# Mouse_Send_SCH.net
KiCad netlist of a schematic drawn in Altium Designer
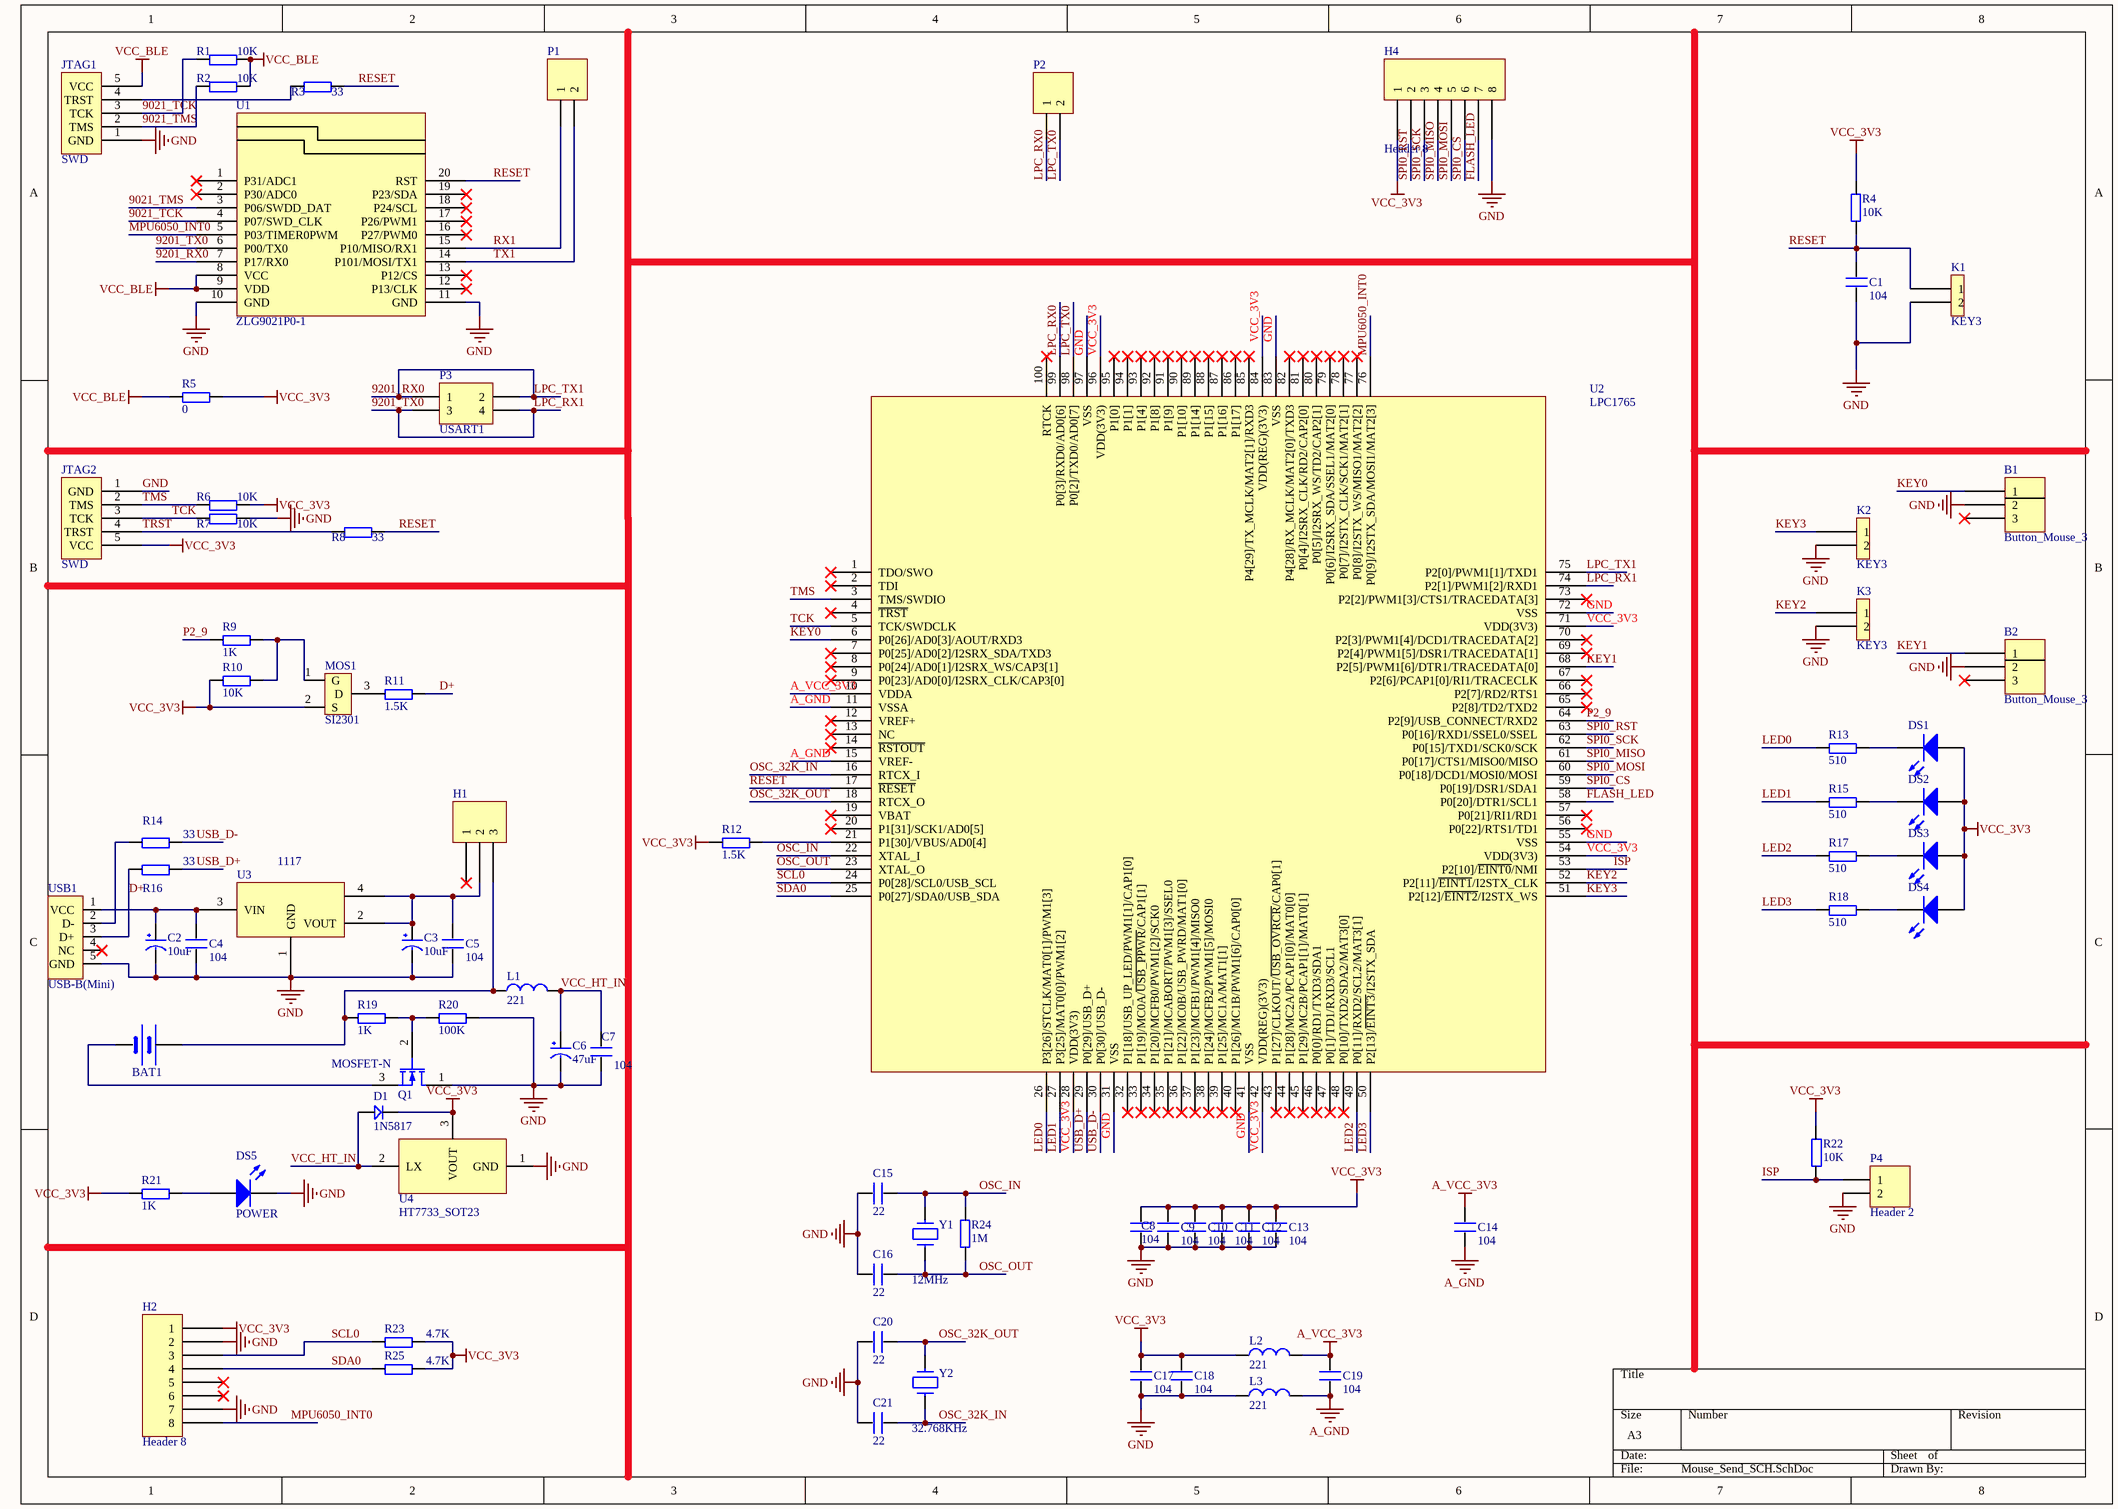
[diagram p0: Mouse_Send_SCH.SchDoc]

(export (version "E")
  (design (tool "Eeschema 10.0.6"))
  (components
    (comp (ref "B1")
      (value "Button_Mouse_3")
      (footprint "Button_Mouse_3")
      (libsource (lib "MY_SCH_Lib") (part "Button_Mouse_3"))
    )
    (comp (ref "B2")
      (value "Button_Mouse_3")
      (footprint "Button_Mouse_3")
      (libsource (lib "MY_SCH_Lib") (part "Button_Mouse_3"))
    )
    (comp (ref "BAT1") (value "BATT") (footprint "BAT_NUM5_2") (libsource (lib "MY_SCH_Lib") (part "BAT")))
    (comp (ref "C1") (value "104") (footprint "0603P") (libsource (lib "MY_SCH_Lib") (part "C")))
    (comp (ref "C2") (value "10uF") (footprint "TAJ_A") (libsource (lib "MY_SCH_Lib") (part "CAP")))
    (comp (ref "C3") (value "10uF") (footprint "TAJ_A") (libsource (lib "MY_SCH_Lib") (part "CAP")))
    (comp (ref "C4") (value "104") (footprint "0603P") (libsource (lib "MY_SCH_Lib") (part "C")))
    (comp (ref "C5") (value "104") (footprint "0603P") (libsource (lib "MY_SCH_Lib") (part "C")))
    (comp (ref "C6") (value "47uF") (footprint "TAJ_A") (libsource (lib "MY_SCH_Lib") (part "CAP")))
    (comp (ref "C7") (value "104") (footprint "0603P") (libsource (lib "MY_SCH_Lib") (part "C")))
    (comp (ref "C8") (value "104") (footprint "0603P") (libsource (lib "MY_SCH_Lib") (part "C")))
    (comp (ref "C9") (value "104") (footprint "0603P") (libsource (lib "MY_SCH_Lib") (part "C")))
    (comp (ref "C10") (value "104") (footprint "0603P") (libsource (lib "MY_SCH_Lib") (part "C")))
    (comp (ref "C11") (value "104") (footprint "0603P") (libsource (lib "MY_SCH_Lib") (part "C")))
    (comp (ref "C12") (value "104") (footprint "0603P") (libsource (lib "MY_SCH_Lib") (part "C")))
    (comp (ref "C13") (value "104") (footprint "0603P") (libsource (lib "MY_SCH_Lib") (part "C")))
    (comp (ref "C14") (value "104") (footprint "0603P") (libsource (lib "MY_SCH_Lib") (part "C")))
    (comp (ref "C15") (value "22") (footprint "0603P") (libsource (lib "MY_SCH_Lib") (part "C")))
    (comp (ref "C16") (value "22") (footprint "0603P") (libsource (lib "MY_SCH_Lib") (part "C")))
    (comp (ref "C17") (value "104") (footprint "0603P") (libsource (lib "MY_SCH_Lib") (part "C")))
    (comp (ref "C18") (value "104") (footprint "0603P") (libsource (lib "MY_SCH_Lib") (part "C")))
    (comp (ref "C19") (value "104") (footprint "0603P") (libsource (lib "MY_SCH_Lib") (part "C")))
    (comp (ref "C20") (value "22") (footprint "0603P") (libsource (lib "MY_SCH_Lib") (part "C")))
    (comp (ref "C21") (value "22") (footprint "0603P") (libsource (lib "MY_SCH_Lib") (part "C")))
    (comp (ref "D1") (value "1N5817") (footprint "DIODE_SOP") (libsource (lib "MY_SCH_Lib") (part "D")))
    (comp (ref "DS1")
      (value "~")
      (footprint "SMDLED")
      (description "Typical RED, GREEN, YELLOW, AMBER GaAs LED")
      (fields (field (name "PUBLISHER") "Altium Limited"))
      (libsource (lib "MY_SCH_Lib") (part "LED2"))
    )
    (comp (ref "DS2")
      (value "~")
      (footprint "SMDLED")
      (description "Typical RED, GREEN, YELLOW, AMBER GaAs LED")
      (fields (field (name "PUBLISHER") "Altium Limited"))
      (libsource (lib "MY_SCH_Lib") (part "LED2"))
    )
    (comp (ref "DS3")
      (value "~")
      (footprint "SMDLED")
      (description "Typical RED, GREEN, YELLOW, AMBER GaAs LED")
      (fields (field (name "PUBLISHER") "Altium Limited"))
      (libsource (lib "MY_SCH_Lib") (part "LED2"))
    )
    (comp (ref "DS4")
      (value "~")
      (footprint "SMDLED")
      (description "Typical RED, GREEN, YELLOW, AMBER GaAs LED")
      (fields (field (name "PUBLISHER") "Altium Limited"))
      (libsource (lib "MY_SCH_Lib") (part "LED2"))
    )
    (comp (ref "DS5")
      (value "POWER")
      (footprint "SMDLED")
      (description "Typical RED, GREEN, YELLOW, AMBER GaAs LED")
      (fields (field (name "PUBLISHER") "Altium Limited"))
      (libsource (lib "MY_SCH_Lib") (part "LED2"))
    )
    (comp (ref "H1") (value "~") (footprint "KEY_B") (libsource (lib "MY_SCH_Lib") (part "Header 3")))
    (comp (ref "H2")
      (value "Header 8")
      (footprint "Header 8")
      (libsource (lib "MY_SCH_Lib") (part "Header 8"))
    )
    (comp (ref "H4") (value "Header 8") (footprint "Header 8") (libsource (lib "") (part "Header 8_1")))
    (comp (ref "JTAG1") (value "SWD") (footprint "HEAD5") (libsource (lib "MY_SCH_Lib") (part "SWD")))
    (comp (ref "JTAG2") (value "SWD") (footprint "HEAD5") (libsource (lib "") (part "SWD_1")))
    (comp (ref "K1") (value "KEY3") (footprint "KEY2") (libsource (lib "MY_SCH_Lib") (part "KEY3")))
    (comp (ref "K2") (value "KEY3") (footprint "KEY2") (libsource (lib "MY_SCH_Lib") (part "KEY3")))
    (comp (ref "K3") (value "KEY3") (footprint "KEY2") (libsource (lib "MY_SCH_Lib") (part "KEY3")))
    (comp (ref "L1") (value "221") (footprint "0603P") (libsource (lib "MY_SCH_Lib") (part "Inductor")))
    (comp (ref "L2") (value "221") (footprint "0603P") (libsource (lib "MY_SCH_Lib") (part "Inductor")))
    (comp (ref "L3") (value "221") (footprint "0603P") (libsource (lib "MY_SCH_Lib") (part "Inductor")))
    (comp (ref "MOS1")
      (value "SI2301")
      (footprint "SOT-23")
      (description "IRLML6401/SI2301")
      (libsource (lib "MY_SCH_Lib") (part "MOS-P"))
    )
    (comp (ref "P1")
      (value "~")
      (footprint "HDR1X2")
      (fields (field (name "PUBLISHER") "Altium Limited"))
      (libsource (lib "") (part "Header 2_1"))
    )
    (comp (ref "P2")
      (value "~")
      (footprint "HDR1X2")
      (fields (field (name "PUBLISHER") "Altium Limited"))
      (libsource (lib "") (part "Header 2_1"))
    )
    (comp (ref "P3")
      (value "USART1")
      (footprint "HDR2X2")
      (description "Header, 2-Pin, Dual row")
      (fields (field (name "PUBLISHER") "Altium Limited"))
      (libsource (lib "MY_SCH_Lib") (part "Header 2X2"))
    )
    (comp (ref "P4")
      (value "Header 2")
      (footprint "HDR1X2")
      (fields (field (name "PUBLISHER") "Altium Limited"))
      (libsource (lib "MY_SCH_Lib") (part "Header 2"))
    )
    (comp (ref "Q1")
      (value "MOSFET-N")
      (footprint "MOSFET_SOT23")
      (description "N-Channel MOSFET")
      (fields (field (name "PUBLISHER") "Altium Limited"))
      (libsource (lib "Miscellaneous Devices") (part "MOSFET-N"))
    )
    (comp (ref "R1") (value "10K") (footprint "0603P") (libsource (lib "MY_SCH_Lib") (part "R")))
    (comp (ref "R2") (value "10K") (footprint "0603P") (libsource (lib "MY_SCH_Lib") (part "R")))
    (comp (ref "R3") (value "33") (footprint "0603P") (libsource (lib "MY_SCH_Lib") (part "R")))
    (comp (ref "R4") (value "10K") (footprint "0603P") (libsource (lib "MY_SCH_Lib") (part "R")))
    (comp (ref "R5") (value "0") (footprint "0603P") (libsource (lib "MY_SCH_Lib") (part "R")))
    (comp (ref "R6") (value "10K") (footprint "0603P") (libsource (lib "MY_SCH_Lib") (part "R")))
    (comp (ref "R7") (value "10K") (footprint "0603P") (libsource (lib "MY_SCH_Lib") (part "R")))
    (comp (ref "R8") (value "33") (footprint "0603P") (libsource (lib "MY_SCH_Lib") (part "R")))
    (comp (ref "R9") (value "1K") (footprint "0603P") (libsource (lib "MY_SCH_Lib") (part "R")))
    (comp (ref "R10") (value "10K") (footprint "0603P") (libsource (lib "MY_SCH_Lib") (part "R")))
    (comp (ref "R11") (value "1.5K") (footprint "0603P") (libsource (lib "MY_SCH_Lib") (part "R")))
    (comp (ref "R12") (value "1.5K") (footprint "0603P") (libsource (lib "MY_SCH_Lib") (part "R")))
    (comp (ref "R13") (value "510") (footprint "0603P") (libsource (lib "MY_SCH_Lib") (part "R")))
    (comp (ref "R14") (value "33") (footprint "0603P") (libsource (lib "MY_SCH_Lib") (part "R")))
    (comp (ref "R15") (value "510") (footprint "0603P") (libsource (lib "MY_SCH_Lib") (part "R")))
    (comp (ref "R16") (value "33") (footprint "0603P") (libsource (lib "MY_SCH_Lib") (part "R")))
    (comp (ref "R17") (value "510") (footprint "0603P") (libsource (lib "MY_SCH_Lib") (part "R")))
    (comp (ref "R18") (value "510") (footprint "0603P") (libsource (lib "MY_SCH_Lib") (part "R")))
    (comp (ref "R19") (value "1K") (footprint "0603P") (libsource (lib "MY_SCH_Lib") (part "R")))
    (comp (ref "R20") (value "100K") (footprint "0603P") (libsource (lib "MY_SCH_Lib") (part "R")))
    (comp (ref "R21") (value "1K") (footprint "0603P") (libsource (lib "MY_SCH_Lib") (part "R")))
    (comp (ref "R22") (value "10K") (footprint "0603P") (libsource (lib "MY_SCH_Lib") (part "R")))
    (comp (ref "R23") (value "4.7K") (footprint "0603P") (libsource (lib "MY_SCH_Lib") (part "R")))
    (comp (ref "R24") (value "1M") (footprint "0603P") (libsource (lib "MY_SCH_Lib") (part "R")))
    (comp (ref "R25") (value "4.7K") (footprint "0603P") (libsource (lib "MY_SCH_Lib") (part "R")))
    (comp (ref "U1")
      (value "ZLG9021P0-1")
      (footprint "ZLG9021P0-1")
      (libsource (lib "MY_SCH_Lib") (part "ZLG9021P0-1"))
    )
    (comp (ref "U2")
      (value "LPC1765")
      (footprint "TQFP-100")
      (libsource (lib "LPC17xx_System_Sch_AD") (part "LPC1765"))
    )
    (comp (ref "U3") (value "1117") (footprint "AMS1117") (libsource (lib "MY_SCH_Lib") (part "1117")))
    (comp (ref "U4")
      (value "HT7733_SOT23")
      (footprint "SOT-23")
      (libsource (lib "LPC17xx_System_Sch_AD") (part "HT7733_SOT23"))
    )
    (comp (ref "USB1")
      (value "USB-B(Mini)")
      (footprint "USB/SM0.8-6H5")
      (libsource (lib "MY_SCH_Lib") (part "USB5"))
    )
    (comp (ref "Y1")
      (value "12MHz")
      (footprint "XTAL_US")
      (description "Crystal")
      (libsource (lib "LPC17xx_System_Sch_AD") (part "CRYSTAL"))
    )
    (comp (ref "Y2")
      (value "32.768KHz")
      (footprint "CRY-32")
      (description "Crystal")
      (libsource (lib "LPC17xx_System_Sch_AD") (part "CRYSTAL"))
    )
  )
  (nets
    (net (code "1") (name "/9021_TCK") (class "Default")
      (node (ref "JTAG1") (pin "3") (pinfunction "TCK_3") (pintype "passive"))
      (node (ref "R1") (pin "1") (pintype "passive"))
      (node (ref "U1") (pin "4") (pinfunction "P07/SWD_CLK_4") (pintype "passive"))
    )
    (net (code "2") (name "/9021_TMS") (class "Default")
      (node (ref "JTAG1") (pin "2") (pinfunction "TMS_2") (pintype "passive"))
      (node (ref "R2") (pin "1") (pintype "passive"))
      (node (ref "U1") (pin "3") (pinfunction "P06/SWDD_DAT_3") (pintype "passive"))
    )
    (net (code "3") (name "/9201_RX0") (class "Default")
      (node (ref "P3") (pin "1") (pinfunction "1_1") (pintype "passive"))
      (node (ref "P3") (pin "2") (pinfunction "2_2") (pintype "passive"))
      (node (ref "U1") (pin "7") (pinfunction "P17/RX0_7") (pintype "passive"))
      (node (ref "U2") (pin "75") (pinfunction "P2[0]/PWM1[1]/TXD1_75") (pintype "passive"))
    )
    (net (code "4") (name "/9201_TX0") (class "Default")
      (node (ref "P3") (pin "3") (pinfunction "3_3") (pintype "passive"))
      (node (ref "P3") (pin "4") (pinfunction "4_4") (pintype "passive"))
      (node (ref "U1") (pin "6") (pinfunction "P00/TX0_6") (pintype "passive"))
      (node (ref "U2") (pin "74") (pinfunction "P2[1]/PWM1[2]/RXD1_74") (pintype "passive"))
    )
    (net (code "5") (name "/D+") (class "Default")
      (node (ref "R11") (pin "2") (pintype "passive"))
      (node (ref "R16") (pin "1") (pintype "passive"))
      (node (ref "USB1") (pin "3") (pinfunction "D+_3") (pintype "passive"))
    )
    (net (code "6") (name "/FLASH_LED") (class "Default")
      (node (ref "H4") (pin "7") (pinfunction "7_7") (pintype "passive"))
      (node (ref "U2") (pin "58") (pinfunction "P0[20]/DTR1/SCL1_58") (pintype "passive"))
    )
    (net (code "7") (name "/ISP") (class "Default")
      (node (ref "P4") (pin "1") (pinfunction "1_1") (pintype "passive"))
      (node (ref "R22") (pin "1") (pintype "passive"))
      (node (ref "U2") (pin "53") (pinfunction "P2[10]/~{EINT0}/NMI_53") (pintype "passive"))
    )
    (net (code "8") (name "/KEY0") (class "Default")
      (node (ref "B1") (pin "1") (pinfunction "1_1") (pintype "passive"))
      (node (ref "U2") (pin "6") (pinfunction "P0[26]/AD0[3]/AOUT/RXD3_6") (pintype "passive"))
    )
    (net (code "9") (name "/KEY1") (class "Default")
      (node (ref "B2") (pin "1") (pinfunction "1_1") (pintype "passive"))
      (node (ref "U2") (pin "68") (pinfunction "P2[5]/PWM1[6]/DTR1/TRACEDATA[0]_68") (pintype "passive"))
    )
    (net (code "10") (name "/KEY2") (class "Default")
      (node (ref "K3") (pin "1") (pinfunction "1_1") (pintype "passive"))
      (node (ref "U2") (pin "52") (pinfunction "P2[11]/~{EINT1}/I2STX_CLK_52") (pintype "passive"))
    )
    (net (code "11") (name "/KEY3") (class "Default")
      (node (ref "K2") (pin "1") (pinfunction "1_1") (pintype "passive"))
      (node (ref "U2") (pin "51") (pinfunction "P2[12]/~{EINT2}/I2STX_WS_51") (pintype "passive"))
    )
    (net (code "12") (name "/LED0") (class "Default")
      (node (ref "R13") (pin "1") (pintype "passive"))
      (node (ref "U2") (pin "26") (pinfunction "P3[26]/STCLK/MAT0[1]/PWM1[3]_26") (pintype "passive"))
    )
    (net (code "13") (name "/LED1") (class "Default")
      (node (ref "R15") (pin "1") (pintype "passive"))
      (node (ref "U2") (pin "27") (pinfunction "P3[25]/MAT0[0]/PWM1[2]_27") (pintype "passive"))
    )
    (net (code "14") (name "/LED2") (class "Default")
      (node (ref "R17") (pin "1") (pintype "passive"))
      (node (ref "U2") (pin "49") (pinfunction "P0[11]/RXD2/SCL2/MAT3[1]_49") (pintype "passive"))
    )
    (net (code "15") (name "/LED3") (class "Default")
      (node (ref "R18") (pin "1") (pintype "passive"))
      (node (ref "U2") (pin "50") (pinfunction "P2[13]/~{EINT3}/I2STX_SDA_50") (pintype "passive"))
    )
    (net (code "16") (name "/LPC_RX0") (class "Default")
      (node (ref "P2") (pin "1") (pinfunction "1_1") (pintype "passive"))
      (node (ref "U2") (pin "99") (pinfunction "P0[3]/RXD0/AD0[6]_99") (pintype "passive"))
    )
    (net (code "17") (name "/LPC_TX0") (class "Default")
      (node (ref "P2") (pin "2") (pinfunction "2_2") (pintype "passive"))
      (node (ref "U2") (pin "98") (pinfunction "P0[2]/TXD0/AD0[7]_98") (pintype "passive"))
    )
    (net (code "18") (name "/MPU6050_INT0") (class "Default")
      (node (ref "H2") (pin "8") (pinfunction "8_8") (pintype "passive"))
      (node (ref "U1") (pin "5") (pinfunction "P03/TIMER0PWM_5") (pintype "passive"))
      (node (ref "U2") (pin "76") (pinfunction "P0[9]/I2STX_SDA/MOSI1/MAT2[3]_76") (pintype "passive"))
    )
    (net (code "19") (name "/OSC_32K_IN") (class "Default")
      (node (ref "C21") (pin "2") (pintype "passive"))
      (node (ref "U2") (pin "16") (pinfunction "RTCX_I_16") (pintype "passive"))
      (node (ref "Y2") (pin "1") (pinfunction "1_1") (pintype "passive"))
    )
    (net (code "20") (name "/OSC_32K_OUT") (class "Default")
      (node (ref "C20") (pin "2") (pintype "passive"))
      (node (ref "U2") (pin "18") (pinfunction "RTCX_O_18") (pintype "passive"))
      (node (ref "Y2") (pin "2") (pinfunction "2_2") (pintype "passive"))
    )
    (net (code "21") (name "/OSC_IN") (class "Default")
      (node (ref "C15") (pin "2") (pintype "passive"))
      (node (ref "R24") (pin "1") (pintype "passive"))
      (node (ref "U2") (pin "22") (pinfunction "XTAL_I_22") (pintype "passive"))
      (node (ref "Y1") (pin "2") (pinfunction "2_2") (pintype "passive"))
    )
    (net (code "22") (name "/OSC_OUT") (class "Default")
      (node (ref "C16") (pin "2") (pintype "passive"))
      (node (ref "R24") (pin "2") (pintype "passive"))
      (node (ref "U2") (pin "23") (pinfunction "XTAL_O_23") (pintype "passive"))
      (node (ref "Y1") (pin "1") (pinfunction "1_1") (pintype "passive"))
    )
    (net (code "23") (name "/P2_9") (class "Default")
      (node (ref "R9") (pin "1") (pintype "passive"))
      (node (ref "U2") (pin "64") (pinfunction "P2[9]/USB_CONNECT/RXD2_64") (pintype "passive"))
    )
    (net (code "24") (name "/RESET") (class "Default")
      (node (ref "C1") (pin "2") (pintype "passive"))
      (node (ref "K1") (pin "1") (pinfunction "1_1") (pintype "passive"))
      (node (ref "R3") (pin "2") (pintype "passive"))
      (node (ref "R4") (pin "1") (pintype "passive"))
      (node (ref "R8") (pin "2") (pintype "passive"))
      (node (ref "U1") (pin "20") (pinfunction "RST_20") (pintype "passive"))
      (node (ref "U2") (pin "17") (pinfunction "~{RESET}_17") (pintype "passive"))
    )
    (net (code "25") (name "/RX1") (class "Default")
      (node (ref "P1") (pin "1") (pinfunction "1_1") (pintype "passive"))
      (node (ref "U1") (pin "15") (pinfunction "P10/MISO/RX1_15") (pintype "passive"))
    )
    (net (code "26") (name "/SCL0") (class "Default")
      (node (ref "H2") (pin "3") (pinfunction "3_3") (pintype "passive"))
      (node (ref "R23") (pin "1") (pintype "passive"))
      (node (ref "U2") (pin "24") (pinfunction "P0[28]/SCL0/USB_SCL_24") (pintype "passive"))
    )
    (net (code "27") (name "/SDA0") (class "Default")
      (node (ref "H2") (pin "4") (pinfunction "4_4") (pintype "passive"))
      (node (ref "R25") (pin "1") (pintype "passive"))
      (node (ref "U2") (pin "25") (pinfunction "P0[27]/SDA0/USB_SDA_25") (pintype "passive"))
    )
    (net (code "28") (name "/SPI0_CS") (class "Default")
      (node (ref "H4") (pin "6") (pinfunction "6_6") (pintype "passive"))
      (node (ref "U2") (pin "59") (pinfunction "P0[19]/DSR1/SDA1_59") (pintype "passive"))
    )
    (net (code "29") (name "/SPI0_MISO") (class "Default")
      (node (ref "H4") (pin "4") (pinfunction "4_4") (pintype "passive"))
      (node (ref "U2") (pin "61") (pinfunction "P0[17]/CTS1/MISO0/MISO_61") (pintype "passive"))
    )
    (net (code "30") (name "/SPI0_MOSI") (class "Default")
      (node (ref "H4") (pin "5") (pinfunction "5_5") (pintype "passive"))
      (node (ref "U2") (pin "60") (pinfunction "P0[18]/DCD1/MOSI0/MOSI_60") (pintype "passive"))
    )
    (net (code "31") (name "/SPI0_RST") (class "Default")
      (node (ref "H4") (pin "2") (pinfunction "2_2") (pintype "passive"))
      (node (ref "U2") (pin "63") (pinfunction "P0[16]/RXD1/SSEL0/SSEL_63") (pintype "passive"))
    )
    (net (code "32") (name "/SPI0_SCK") (class "Default")
      (node (ref "H4") (pin "3") (pinfunction "3_3") (pintype "passive"))
      (node (ref "U2") (pin "62") (pinfunction "P0[15]/TXD1/SCK0/SCK_62") (pintype "passive"))
    )
    (net (code "33") (name "/TCK") (class "Default")
      (node (ref "JTAG2") (pin "3") (pinfunction "TCK_3") (pintype "passive"))
      (node (ref "R7") (pin "1") (pintype "passive"))
      (node (ref "U2") (pin "5") (pinfunction "TCK/SWDCLK_5") (pintype "passive"))
    )
    (net (code "34") (name "/TMS") (class "Default")
      (node (ref "JTAG2") (pin "2") (pinfunction "TMS_2") (pintype "passive"))
      (node (ref "R6") (pin "1") (pintype "passive"))
      (node (ref "U2") (pin "3") (pinfunction "TMS/SWDIO_3") (pintype "passive"))
    )
    (net (code "35") (name "/TRST") (class "Default")
      (node (ref "JTAG2") (pin "4") (pinfunction "TRST_4") (pintype "passive"))
      (node (ref "R8") (pin "1") (pintype "passive"))
    )
    (net (code "36") (name "/TX1") (class "Default")
      (node (ref "P1") (pin "2") (pinfunction "2_2") (pintype "passive"))
      (node (ref "U1") (pin "14") (pinfunction "P101/MOSI/TX1_14") (pintype "passive"))
    )
    (net (code "37") (name "/USB_D+") (class "Default")
      (node (ref "R16") (pin "2") (pintype "passive"))
      (node (ref "U2") (pin "29") (pinfunction "P0[29]/USB_D+_29") (pintype "passive"))
    )
    (net (code "38") (name "/USB_D-") (class "Default")
      (node (ref "R14") (pin "2") (pintype "passive"))
      (node (ref "U2") (pin "30") (pinfunction "P0[30]/USB_D-_30") (pintype "passive"))
    )
    (net (code "39") (name "/VCC_HT_IN") (class "Default")
      (node (ref "C6") (pin "1") (pinfunction "VCC_1") (pintype "passive"))
      (node (ref "C7") (pin "2") (pintype "passive"))
      (node (ref "D1") (pin "1") (pintype "passive"))
      (node (ref "L1") (pin "2") (pinfunction "2_2") (pintype "passive"))
      (node (ref "U4") (pin "2") (pinfunction "LX_2") (pintype "passive"))
    )
    (net (code "40") (name "A_GND") (class "Default")
      (node (ref "C14") (pin "2") (pintype "passive"))
      (node (ref "C19") (pin "1") (pintype "passive"))
      (node (ref "L3") (pin "2") (pinfunction "2_2") (pintype "passive"))
      (node (ref "U2") (pin "11") (pinfunction "VSSA_11") (pintype "passive"))
      (node (ref "U2") (pin "15") (pinfunction "VREF-_15") (pintype "passive"))
    )
    (net (code "41") (name "A_VCC_3V3") (class "Default")
      (node (ref "C14") (pin "1") (pintype "passive"))
      (node (ref "C19") (pin "2") (pintype "passive"))
      (node (ref "L2") (pin "2") (pinfunction "2_2") (pintype "passive"))
      (node (ref "U2") (pin "10") (pinfunction "VDDA_10") (pintype "passive"))
    )
    (net (code "42") (name "GND") (class "Default")
      (node (ref "B1") (pin "2") (pinfunction "2_2") (pintype "passive"))
      (node (ref "B2") (pin "2") (pinfunction "2_2") (pintype "passive"))
      (node (ref "C1") (pin "1") (pintype "passive"))
      (node (ref "C10") (pin "2") (pintype "passive"))
      (node (ref "C11") (pin "2") (pintype "passive"))
      (node (ref "C12") (pin "2") (pintype "passive"))
      (node (ref "C13") (pin "2") (pintype "passive"))
      (node (ref "C15") (pin "1") (pintype "passive"))
      (node (ref "C16") (pin "1") (pintype "passive"))
      (node (ref "C17") (pin "1") (pintype "passive"))
      (node (ref "C18") (pin "1") (pintype "passive"))
      (node (ref "C2") (pin "2") (pinfunction "GND_2") (pintype "passive"))
      (node (ref "C20") (pin "1") (pintype "passive"))
      (node (ref "C21") (pin "1") (pintype "passive"))
      (node (ref "C3") (pin "2") (pinfunction "GND_2") (pintype "passive"))
      (node (ref "C4") (pin "1") (pintype "passive"))
      (node (ref "C5") (pin "1") (pintype "passive"))
      (node (ref "C6") (pin "2") (pinfunction "GND_2") (pintype "passive"))
      (node (ref "C7") (pin "1") (pintype "passive"))
      (node (ref "C8") (pin "2") (pintype "passive"))
      (node (ref "C9") (pin "2") (pintype "passive"))
      (node (ref "DS5") (pin "2") (pinfunction "K_2") (pintype "passive"))
      (node (ref "H2") (pin "2") (pinfunction "2_2") (pintype "passive"))
      (node (ref "H2") (pin "7") (pinfunction "7_7") (pintype "passive"))
      (node (ref "H4") (pin "8") (pinfunction "8_8") (pintype "passive"))
      (node (ref "JTAG1") (pin "1") (pinfunction "GND_1") (pintype "passive"))
      (node (ref "JTAG2") (pin "1") (pinfunction "GND_1") (pintype "passive"))
      (node (ref "K1") (pin "2") (pinfunction "2_2") (pintype "passive"))
      (node (ref "K2") (pin "2") (pinfunction "2_2") (pintype "passive"))
      (node (ref "K3") (pin "2") (pinfunction "2_2") (pintype "passive"))
      (node (ref "L3") (pin "1") (pinfunction "1_1") (pintype "passive"))
      (node (ref "P4") (pin "2") (pinfunction "2_2") (pintype "passive"))
      (node (ref "Q1") (pin "1") (pinfunction "D_1") (pintype "passive"))
      (node (ref "R20") (pin "2") (pintype "passive"))
      (node (ref "R7") (pin "2") (pintype "passive"))
      (node (ref "U1") (pin "10") (pinfunction "GND_10") (pintype "passive"))
      (node (ref "U1") (pin "11") (pinfunction "GND_11") (pintype "passive"))
      (node (ref "U2") (pin "31") (pinfunction "VSS_31") (pintype "passive"))
      (node (ref "U2") (pin "41") (pinfunction "VSS_41") (pintype "passive"))
      (node (ref "U2") (pin "55") (pinfunction "VSS_55") (pintype "passive"))
      (node (ref "U2") (pin "72") (pinfunction "VSS_72") (pintype "passive"))
      (node (ref "U2") (pin "83") (pinfunction "VSS_83") (pintype "passive"))
      (node (ref "U2") (pin "97") (pinfunction "VSS_97") (pintype "passive"))
      (node (ref "U3") (pin "1") (pinfunction "GND_1") (pintype "passive"))
      (node (ref "U4") (pin "1") (pinfunction "GND_1") (pintype "passive"))
      (node (ref "USB1") (pin "5") (pinfunction "GND_5") (pintype "passive"))
    )
    (net (code "43") (name "Net-(BAT1-GND)") (class "Default")
      (node (ref "BAT1") (pin "2") (pinfunction "GND_2") (pintype "passive"))
      (node (ref "Q1") (pin "3") (pinfunction "S_3") (pintype "passive"))
    )
    (net (code "44") (name "Net-(BAT1-VCC)") (class "Default")
      (node (ref "BAT1") (pin "1") (pinfunction "VCC_1") (pintype "passive"))
      (node (ref "H1") (pin "3") (pinfunction "3_3") (pintype "passive"))
      (node (ref "L1") (pin "1") (pinfunction "1_1") (pintype "passive"))
      (node (ref "R19") (pin "1") (pintype "passive"))
    )
    (net (code "45") (name "Net-(C2-VCC)") (class "Default")
      (node (ref "C2") (pin "1") (pinfunction "VCC_1") (pintype "passive"))
      (node (ref "C4") (pin "2") (pintype "passive"))
      (node (ref "U3") (pin "3") (pinfunction "VIN_3") (pintype "passive"))
      (node (ref "USB1") (pin "1") (pinfunction "VCC_1") (pintype "passive"))
    )
    (net (code "46") (name "Net-(C3-VCC)") (class "Default")
      (node (ref "C3") (pin "1") (pinfunction "VCC_1") (pintype "passive"))
      (node (ref "C5") (pin "2") (pintype "passive"))
      (node (ref "H1") (pin "2") (pinfunction "2_2") (pintype "passive"))
      (node (ref "U3") (pin "2") (pinfunction "VOUT_2") (pintype "passive"))
      (node (ref "U3") (pin "4") (pinfunction "4_4") (pintype "passive"))
    )
    (net (code "47") (name "Net-(DS1-K)") (class "Default")
      (node (ref "DS1") (pin "2") (pinfunction "K_2") (pintype "passive"))
      (node (ref "R13") (pin "2") (pintype "passive"))
    )
    (net (code "48") (name "Net-(DS2-K)") (class "Default")
      (node (ref "DS2") (pin "2") (pinfunction "K_2") (pintype "passive"))
      (node (ref "R15") (pin "2") (pintype "passive"))
    )
    (net (code "49") (name "Net-(DS3-K)") (class "Default")
      (node (ref "DS3") (pin "2") (pinfunction "K_2") (pintype "passive"))
      (node (ref "R17") (pin "2") (pintype "passive"))
    )
    (net (code "50") (name "Net-(DS4-K)") (class "Default")
      (node (ref "DS4") (pin "2") (pinfunction "K_2") (pintype "passive"))
      (node (ref "R18") (pin "2") (pintype "passive"))
    )
    (net (code "51") (name "Net-(DS5-A)") (class "Default")
      (node (ref "DS5") (pin "1") (pinfunction "A_1") (pintype "passive"))
      (node (ref "R21") (pin "2") (pintype "passive"))
    )
    (net (code "52") (name "Net-(JTAG1-TRST)") (class "Default")
      (node (ref "JTAG1") (pin "4") (pinfunction "TRST_4") (pintype "passive"))
      (node (ref "R3") (pin "1") (pintype "passive"))
    )
    (net (code "53") (name "Net-(MOS1-D)") (class "Default")
      (node (ref "MOS1") (pin "3") (pinfunction "D_3") (pintype "passive"))
      (node (ref "R11") (pin "1") (pintype "passive"))
    )
    (net (code "54") (name "Net-(MOS1-G)") (class "Default")
      (node (ref "MOS1") (pin "1") (pinfunction "G_1") (pintype "passive"))
      (node (ref "R10") (pin "2") (pintype "passive"))
      (node (ref "R9") (pin "2") (pintype "passive"))
    )
    (net (code "55") (name "Net-(Q1-G)") (class "Default")
      (node (ref "Q1") (pin "2") (pinfunction "G_2") (pintype "passive"))
      (node (ref "R19") (pin "2") (pintype "passive"))
      (node (ref "R20") (pin "1") (pintype "passive"))
    )
    (net (code "56") (name "Net-(U2-P1[30]{slash}VBUS{slash}AD0[4])") (class "Default")
      (node (ref "R12") (pin "2") (pintype "passive"))
      (node (ref "U2") (pin "21") (pinfunction "P1[30]/VBUS/AD0[4]_21") (pintype "passive"))
    )
    (net (code "57") (name "Net-(USB1-D-)") (class "Default")
      (node (ref "R14") (pin "1") (pintype "passive"))
      (node (ref "USB1") (pin "2") (pinfunction "D-_2") (pintype "passive"))
    )
    (net (code "58") (name "VCC_3V3") (class "Default")
      (node (ref "C10") (pin "1") (pintype "passive"))
      (node (ref "C11") (pin "1") (pintype "passive"))
      (node (ref "C12") (pin "1") (pintype "passive"))
      (node (ref "C13") (pin "1") (pintype "passive"))
      (node (ref "C17") (pin "2") (pintype "passive"))
      (node (ref "C18") (pin "2") (pintype "passive"))
      (node (ref "C8") (pin "1") (pintype "passive"))
      (node (ref "C9") (pin "1") (pintype "passive"))
      (node (ref "D1") (pin "2") (pintype "passive"))
      (node (ref "DS1") (pin "1") (pinfunction "A_1") (pintype "passive"))
      (node (ref "DS2") (pin "1") (pinfunction "A_1") (pintype "passive"))
      (node (ref "DS3") (pin "1") (pinfunction "A_1") (pintype "passive"))
      (node (ref "DS4") (pin "1") (pinfunction "A_1") (pintype "passive"))
      (node (ref "H2") (pin "1") (pinfunction "1_1") (pintype "passive"))
      (node (ref "H4") (pin "1") (pinfunction "1_1") (pintype "passive"))
      (node (ref "JTAG2") (pin "5") (pinfunction "VCC_5") (pintype "passive"))
      (node (ref "L2") (pin "1") (pinfunction "1_1") (pintype "passive"))
      (node (ref "MOS1") (pin "2") (pinfunction "S_2") (pintype "passive"))
      (node (ref "R10") (pin "1") (pintype "passive"))
      (node (ref "R12") (pin "1") (pintype "passive"))
      (node (ref "R21") (pin "1") (pintype "passive"))
      (node (ref "R22") (pin "2") (pintype "passive"))
      (node (ref "R23") (pin "2") (pintype "passive"))
      (node (ref "R25") (pin "2") (pintype "passive"))
      (node (ref "R4") (pin "2") (pintype "passive"))
      (node (ref "R5") (pin "2") (pintype "passive"))
      (node (ref "R6") (pin "2") (pintype "passive"))
      (node (ref "U2") (pin "28") (pinfunction "VDD(3V3)_28") (pintype "passive"))
      (node (ref "U2") (pin "42") (pinfunction "VDD(REG)(3V3)_42") (pintype "passive"))
      (node (ref "U2") (pin "54") (pinfunction "VDD(3V3)_54") (pintype "passive"))
      (node (ref "U2") (pin "71") (pinfunction "VDD(3V3)_71") (pintype "passive"))
      (node (ref "U2") (pin "84") (pinfunction "VDD(REG)(3V3)_84") (pintype "passive"))
      (node (ref "U2") (pin "96") (pinfunction "VDD(3V3)_96") (pintype "passive"))
      (node (ref "U4") (pin "3") (pinfunction "VOUT_3") (pintype "passive"))
    )
    (net (code "59") (name "VCC_BLE") (class "Default")
      (node (ref "JTAG1") (pin "5") (pinfunction "VCC_5") (pintype "passive"))
      (node (ref "R1") (pin "2") (pintype "passive"))
      (node (ref "R2") (pin "2") (pintype "passive"))
      (node (ref "R5") (pin "1") (pintype "passive"))
      (node (ref "U1") (pin "8") (pinfunction "VCC_8") (pintype "passive"))
      (node (ref "U1") (pin "9") (pinfunction "VDD_9") (pintype "passive"))
    )
    (net (code "60") (name "unconnected-(B1-Pad3)") (class "Default")
      (node (ref "B1") (pin "3") (pinfunction "3_3") (pintype "passive+no_connect"))
    )
    (net (code "61") (name "unconnected-(B2-Pad3)") (class "Default")
      (node (ref "B2") (pin "3") (pinfunction "3_3") (pintype "passive+no_connect"))
    )
    (net (code "62") (name "unconnected-(H1-Pad1)") (class "Default")
      (node (ref "H1") (pin "1") (pinfunction "1_1") (pintype "passive+no_connect"))
    )
    (net (code "63") (name "unconnected-(H2-Pad5)") (class "Default")
      (node (ref "H2") (pin "5") (pinfunction "5_5") (pintype "passive+no_connect"))
    )
    (net (code "64") (name "unconnected-(H2-Pad6)") (class "Default")
      (node (ref "H2") (pin "6") (pinfunction "6_6") (pintype "passive+no_connect"))
    )
    (net (code "65") (name "unconnected-(U1-P12{slash}CS-Pad13)") (class "Default")
      (node (ref "U1") (pin "13") (pinfunction "P12/CS_13") (pintype "passive+no_connect"))
    )
    (net (code "66") (name "unconnected-(U1-P13{slash}CLK-Pad12)") (class "Default")
      (node (ref "U1") (pin "12") (pinfunction "P13/CLK_12") (pintype "passive+no_connect"))
    )
    (net (code "67") (name "unconnected-(U1-P23{slash}SDA-Pad19)") (class "Default")
      (node (ref "U1") (pin "19") (pinfunction "P23/SDA_19") (pintype "passive+no_connect"))
    )
    (net (code "68") (name "unconnected-(U1-P24{slash}SCL-Pad18)") (class "Default")
      (node (ref "U1") (pin "18") (pinfunction "P24/SCL_18") (pintype "passive+no_connect"))
    )
    (net (code "69") (name "unconnected-(U1-P26{slash}PWM1-Pad17)") (class "Default")
      (node (ref "U1") (pin "17") (pinfunction "P26/PWM1_17") (pintype "passive+no_connect"))
    )
    (net (code "70") (name "unconnected-(U1-P27{slash}PWM0-Pad16)") (class "Default")
      (node (ref "U1") (pin "16") (pinfunction "P27/PWM0_16") (pintype "passive+no_connect"))
    )
    (net (code "71") (name "unconnected-(U1-P30{slash}ADC0-Pad2)") (class "Default")
      (node (ref "U1") (pin "2") (pinfunction "P30/ADC0_2") (pintype "passive+no_connect"))
    )
    (net (code "72") (name "unconnected-(U1-P31{slash}ADC1-Pad1)") (class "Default")
      (node (ref "U1") (pin "1") (pinfunction "P31/ADC1_1") (pintype "passive+no_connect"))
    )
    (net (code "73") (name "unconnected-(U2-NC-Pad13)") (class "Default")
      (node (ref "U2") (pin "13") (pinfunction "NC_13") (pintype "passive+no_connect"))
    )
    (net (code "74") (name "unconnected-(U2-P0[0]{slash}RD1{slash}TXD3{slash}SDA1-Pad46)") (class "Default")
      (node (ref "U2") (pin "46") (pinfunction "P0[0]/RD1/TXD3/SDA1_46") (pintype "passive+no_connect"))
    )
    (net (code "75") (name "unconnected-(U2-P0[1]{slash}TD1{slash}RXD3{slash}SCL1-Pad47)") (class "Default")
      (node (ref "U2") (pin "47") (pinfunction "P0[1]/TD1/RXD3/SCL1_47") (pintype "passive+no_connect"))
    )
    (net (code "76") (name "unconnected-(U2-P0[4]{slash}I2SRX_CLK{slash}RD2{slash}CAP2[0]-Pad81)") (class "Default")
      (node (ref "U2") (pin "81") (pinfunction "P0[4]/I2SRX_CLK/RD2/CAP2[0]_81") (pintype "passive+no_connect"))
    )
    (net (code "77") (name "unconnected-(U2-P0[5]{slash}I2SRX_WS{slash}TD2{slash}CAP2[1]-Pad80)") (class "Default")
      (node (ref "U2") (pin "80") (pinfunction "P0[5]/I2SRX_WS/TD2/CAP2[1]_80") (pintype "passive+no_connect"))
    )
    (net (code "78") (name "unconnected-(U2-P0[6]{slash}I2SRX_SDA{slash}SSEL1{slash}MAT2[0]-Pad79)") (class "Default")
      (node (ref "U2") (pin "79") (pinfunction "P0[6]/I2SRX_SDA/SSEL1/MAT2[0]_79") (pintype "passive+no_connect"))
    )
    (net (code "79") (name "unconnected-(U2-P0[7]{slash}I2STX_CLK{slash}SCK1{slash}MAT2[1]-Pad78)") (class "Default")
      (node (ref "U2") (pin "78") (pinfunction "P0[7]/I2STX_CLK/SCK1/MAT2[1]_78") (pintype "passive+no_connect"))
    )
    (net (code "80") (name "unconnected-(U2-P0[8]{slash}I2STX_WS{slash}MISO1{slash}MAT2[2]-Pad77)") (class "Default")
      (node (ref "U2") (pin "77") (pinfunction "P0[8]/I2STX_WS/MISO1/MAT2[2]_77") (pintype "passive+no_connect"))
    )
    (net (code "81") (name "unconnected-(U2-P0[10]{slash}TXD2{slash}SDA2{slash}MAT3[0]-Pad48)") (class "Default")
      (node (ref "U2") (pin "48") (pinfunction "P0[10]/TXD2/SDA2/MAT3[0]_48") (pintype "passive+no_connect"))
    )
    (net (code "82") (name "unconnected-(U2-P0[21]{slash}RI1{slash}RD1-Pad57)") (class "Default")
      (node (ref "U2") (pin "57") (pinfunction "P0[21]/RI1/RD1_57") (pintype "passive+no_connect"))
    )
    (net (code "83") (name "unconnected-(U2-P0[22]{slash}RTS1{slash}TD1-Pad56)") (class "Default")
      (node (ref "U2") (pin "56") (pinfunction "P0[22]/RTS1/TD1_56") (pintype "passive+no_connect"))
    )
    (net (code "84") (name "unconnected-(U2-P0[23]{slash}AD0[0]{slash}I2SRX_CLK{slash}CAP3[0]-Pad9)") (class "Default")
      (node (ref "U2") (pin "9") (pinfunction "P0[23]/AD0[0]/I2SRX_CLK/CAP3[0]_9") (pintype "passive+no_connect"))
    )
    (net (code "85") (name "unconnected-(U2-P0[24]{slash}AD0[1]{slash}I2SRX_WS{slash}CAP3[1]-Pad8)") (class "Default")
      (node (ref "U2") (pin "8") (pinfunction "P0[24]/AD0[1]/I2SRX_WS/CAP3[1]_8") (pintype "passive+no_connect"))
    )
    (net (code "86") (name "unconnected-(U2-P0[25]{slash}AD0[2]{slash}I2SRX_SDA{slash}TXD3-Pad7)") (class "Default")
      (node (ref "U2") (pin "7") (pinfunction "P0[25]/AD0[2]/I2SRX_SDA/TXD3_7") (pintype "passive+no_connect"))
    )
    (net (code "87") (name "unconnected-(U2-P1[0]-Pad95)") (class "Default")
      (node (ref "U2") (pin "95") (pinfunction "P1[0]_95") (pintype "passive+no_connect"))
    )
    (net (code "88") (name "unconnected-(U2-P1[1]-Pad94)") (class "Default")
      (node (ref "U2") (pin "94") (pinfunction "P1[1]_94") (pintype "passive+no_connect"))
    )
    (net (code "89") (name "unconnected-(U2-P1[4]-Pad93)") (class "Default")
      (node (ref "U2") (pin "93") (pinfunction "P1[4]_93") (pintype "passive+no_connect"))
    )
    (net (code "90") (name "unconnected-(U2-P1[8]-Pad92)") (class "Default")
      (node (ref "U2") (pin "92") (pinfunction "P1[8]_92") (pintype "passive+no_connect"))
    )
    (net (code "91") (name "unconnected-(U2-P1[9]-Pad91)") (class "Default")
      (node (ref "U2") (pin "91") (pinfunction "P1[9]_91") (pintype "passive+no_connect"))
    )
    (net (code "92") (name "unconnected-(U2-P1[10]-Pad90)") (class "Default")
      (node (ref "U2") (pin "90") (pinfunction "P1[10]_90") (pintype "passive+no_connect"))
    )
    (net (code "93") (name "unconnected-(U2-P1[14]-Pad89)") (class "Default")
      (node (ref "U2") (pin "89") (pinfunction "P1[14]_89") (pintype "passive+no_connect"))
    )
    (net (code "94") (name "unconnected-(U2-P1[15]-Pad88)") (class "Default")
      (node (ref "U2") (pin "88") (pinfunction "P1[15]_88") (pintype "passive+no_connect"))
    )
    (net (code "95") (name "unconnected-(U2-P1[16]-Pad87)") (class "Default")
      (node (ref "U2") (pin "87") (pinfunction "P1[16]_87") (pintype "passive+no_connect"))
    )
    (net (code "96") (name "unconnected-(U2-P1[17]-Pad86)") (class "Default")
      (node (ref "U2") (pin "86") (pinfunction "P1[17]_86") (pintype "passive+no_connect"))
    )
    (net (code "97") (name "unconnected-(U2-P1[18]{slash}USB_UP_LED{slash}PWM1[1]{slash}CAP1[0]-Pad32)") (class "Default")
      (node (ref "U2") (pin "32") (pinfunction "P1[18]/USB_UP_LED/PWM1[1]/CAP1[0]_32") (pintype "passive+no_connect"))
    )
    (net (code "98") (name "unconnected-(U2-P1[19]{slash}MC0A{slash}~{USB_PPWR}{slash}CAP1[1]-Pad33)") (class "Default")
      (node (ref "U2") (pin "33") (pinfunction "P1[19]/MC0A/~{USB_PPWR}/CAP1[1]_33") (pintype "passive+no_connect"))
    )
    (net (code "99") (name "unconnected-(U2-P1[20]{slash}MCFB0{slash}PWM1[2]{slash}SCK0-Pad34)") (class "Default")
      (node (ref "U2") (pin "34") (pinfunction "P1[20]/MCFB0/PWM1[2]/SCK0_34") (pintype "passive+no_connect"))
    )
    (net (code "100") (name "unconnected-(U2-P1[21]{slash}MCABORT{slash}PWM1[3]{slash}SSEL0-Pad35)") (class "Default")
      (node (ref "U2") (pin "35") (pinfunction "P1[21]/MCABORT/PWM1[3]/SSEL0_35") (pintype "passive+no_connect"))
    )
    (net (code "101") (name "unconnected-(U2-P1[22]{slash}MC0B{slash}USB_PWRD{slash}MAT1[0]-Pad36)") (class "Default")
      (node (ref "U2") (pin "36") (pinfunction "P1[22]/MC0B/USB_PWRD/MAT1[0]_36") (pintype "passive+no_connect"))
    )
    (net (code "102") (name "unconnected-(U2-P1[23]{slash}MCFB1{slash}PWM1[4]{slash}MISO0-Pad37)") (class "Default")
      (node (ref "U2") (pin "37") (pinfunction "P1[23]/MCFB1/PWM1[4]/MISO0_37") (pintype "passive+no_connect"))
    )
    (net (code "103") (name "unconnected-(U2-P1[24]{slash}MCFB2{slash}PWM1[5]{slash}MOSI0-Pad38)") (class "Default")
      (node (ref "U2") (pin "38") (pinfunction "P1[24]/MCFB2/PWM1[5]/MOSI0_38") (pintype "passive+no_connect"))
    )
    (net (code "104") (name "unconnected-(U2-P1[25]{slash}MC1A{slash}MAT1[1]-Pad39)") (class "Default")
      (node (ref "U2") (pin "39") (pinfunction "P1[25]/MC1A/MAT1[1]_39") (pintype "passive+no_connect"))
    )
    (net (code "105") (name "unconnected-(U2-P1[26]{slash}MC1B{slash}PWM1[6]{slash}CAP0[0]-Pad40)") (class "Default")
      (node (ref "U2") (pin "40") (pinfunction "P1[26]/MC1B/PWM1[6]/CAP0[0]_40") (pintype "passive+no_connect"))
    )
    (net (code "106") (name "unconnected-(U2-P1[27]{slash}CLKOUT{slash}~{USB_OVRCR}{slash}CAP0[1]-Pad43)") (class "Default")
      (node (ref "U2") (pin "43") (pinfunction "P1[27]/CLKOUT/~{USB_OVRCR}/CAP0[1]_43") (pintype "passive+no_connect"))
    )
    (net (code "107") (name "unconnected-(U2-P1[28]{slash}MC2A{slash}PCAP1[0]{slash}MAT0[0]-Pad44)") (class "Default")
      (node (ref "U2") (pin "44") (pinfunction "P1[28]/MC2A/PCAP1[0]/MAT0[0]_44") (pintype "passive+no_connect"))
    )
    (net (code "108") (name "unconnected-(U2-P1[29]{slash}MC2B{slash}PCAP1[1]{slash}MAT0[1]-Pad45)") (class "Default")
      (node (ref "U2") (pin "45") (pinfunction "P1[29]/MC2B/PCAP1[1]/MAT0[1]_45") (pintype "passive+no_connect"))
    )
    (net (code "109") (name "unconnected-(U2-P1[31]{slash}SCK1{slash}AD0[5]-Pad20)") (class "Default")
      (node (ref "U2") (pin "20") (pinfunction "P1[31]/SCK1/AD0[5]_20") (pintype "passive+no_connect"))
    )
    (net (code "110") (name "unconnected-(U2-P2[2]{slash}PWM1[3]{slash}CTS1{slash}TRACEDATA[3]-Pad73)") (class "Default")
      (node (ref "U2") (pin "73") (pinfunction "P2[2]/PWM1[3]/CTS1/TRACEDATA[3]_73") (pintype "passive+no_connect"))
    )
    (net (code "111") (name "unconnected-(U2-P2[3]{slash}PWM1[4]{slash}DCD1{slash}TRACEDATA[2]-Pad70)") (class "Default")
      (node (ref "U2") (pin "70") (pinfunction "P2[3]/PWM1[4]/DCD1/TRACEDATA[2]_70") (pintype "passive+no_connect"))
    )
    (net (code "112") (name "unconnected-(U2-P2[4]{slash}PWM1[5]{slash}DSR1{slash}TRACEDATA[1]-Pad69)") (class "Default")
      (node (ref "U2") (pin "69") (pinfunction "P2[4]/PWM1[5]/DSR1/TRACEDATA[1]_69") (pintype "passive+no_connect"))
    )
    (net (code "113") (name "unconnected-(U2-P2[6]{slash}PCAP1[0]{slash}RI1{slash}TRACECLK-Pad67)") (class "Default")
      (node (ref "U2") (pin "67") (pinfunction "P2[6]/PCAP1[0]/RI1/TRACECLK_67") (pintype "passive+no_connect"))
    )
    (net (code "114") (name "unconnected-(U2-P2[7]{slash}RD2{slash}RTS1-Pad66)") (class "Default")
      (node (ref "U2") (pin "66") (pinfunction "P2[7]/RD2/RTS1_66") (pintype "passive+no_connect"))
    )
    (net (code "115") (name "unconnected-(U2-P2[8]{slash}TD2{slash}TXD2-Pad65)") (class "Default")
      (node (ref "U2") (pin "65") (pinfunction "P2[8]/TD2/TXD2_65") (pintype "passive+no_connect"))
    )
    (net (code "116") (name "unconnected-(U2-P4[28]{slash}RX_MCLK{slash}MAT2[0]{slash}TXD3-Pad82)") (class "Default")
      (node (ref "U2") (pin "82") (pinfunction "P4[28]/RX_MCLK/MAT2[0]/TXD3_82") (pintype "passive+no_connect"))
    )
    (net (code "117") (name "unconnected-(U2-P4[29]{slash}TX_MCLK{slash}MAT2[1]{slash}RXD3-Pad85)") (class "Default")
      (node (ref "U2") (pin "85") (pinfunction "P4[29]/TX_MCLK/MAT2[1]/RXD3_85") (pintype "passive+no_connect"))
    )
    (net (code "118") (name "unconnected-(U2-RTCK-Pad100)") (class "Default")
      (node (ref "U2") (pin "100") (pinfunction "RTCK_100") (pintype "passive+no_connect"))
    )
    (net (code "119") (name "unconnected-(U2-TDI-Pad2)") (class "Default")
      (node (ref "U2") (pin "2") (pinfunction "TDI_2") (pintype "passive+no_connect"))
    )
    (net (code "120") (name "unconnected-(U2-TDO{slash}SWO-Pad1)") (class "Default")
      (node (ref "U2") (pin "1") (pinfunction "TDO/SWO_1") (pintype "passive+no_connect"))
    )
    (net (code "121") (name "unconnected-(U2-VBAT-Pad19)") (class "Default")
      (node (ref "U2") (pin "19") (pinfunction "VBAT_19") (pintype "passive+no_connect"))
    )
    (net (code "122") (name "unconnected-(U2-VREF+-Pad12)") (class "Default")
      (node (ref "U2") (pin "12") (pinfunction "VREF+_12") (pintype "passive+no_connect"))
    )
    (net (code "123") (name "unconnected-(U2-~{RSTOUT}-Pad14)") (class "Default")
      (node (ref "U2") (pin "14") (pinfunction "~{RSTOUT}_14") (pintype "passive+no_connect"))
    )
    (net (code "124") (name "unconnected-(U2-~{TRST}-Pad4)") (class "Default")
      (node (ref "U2") (pin "4") (pinfunction "~{TRST}_4") (pintype "passive+no_connect"))
    )
    (net (code "125") (name "unconnected-(USB1-NC-Pad4)") (class "Default")
      (node (ref "USB1") (pin "4") (pinfunction "NC_4") (pintype "passive+no_connect"))
    )
  )
)
